# SIM_INTERFACE.net
KiCad netlist of a schematic drawn in Altium Designer
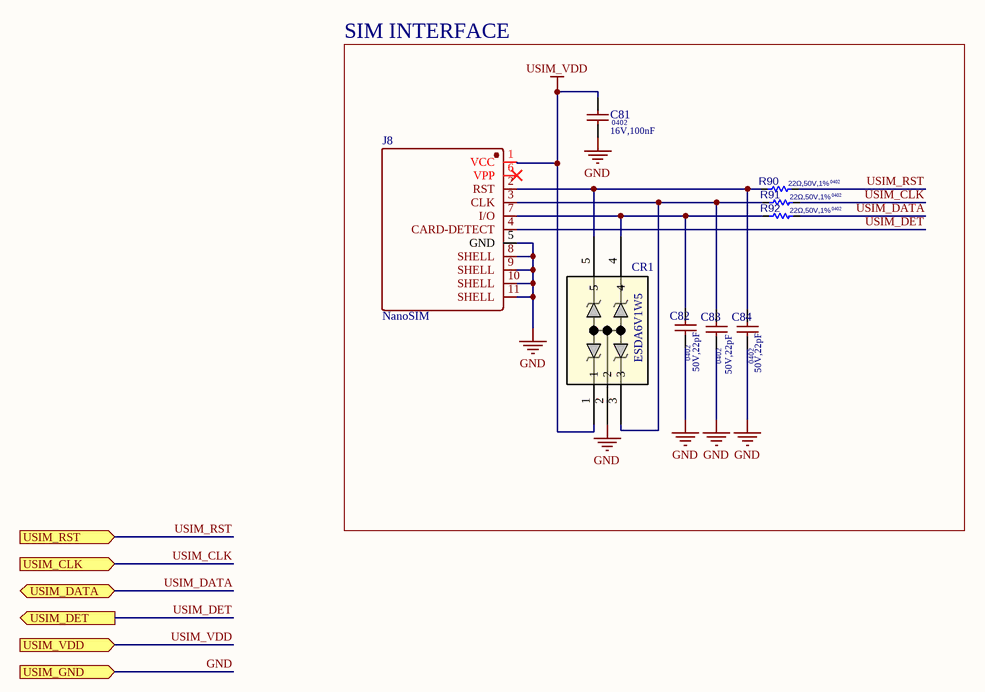
[diagram p0: SIM_INTERFACE.SchDoc]

(export (version "E")
  (design (tool "Eeschema 10.0.6"))
  (components
    (comp (ref "C81")
      (value "16V,100nF")
      (footprint "C0402")
      (description "16V 100nF X7R ±10% 0402 Multilayer Ceramic Capacitors MLCC - SMD/SMT ROHS")
      (fields
        (field (name "MANUFACTURER") "KEMET")
        (field (name "MPN") "CC0603KRX7R9BB104")
        (field (name "PACKAGE") "0402")
      )
      (libsource (lib "RCL") (part "CL05B104KO5NNNC"))
    )
    (comp (ref "C82")
      (value "50V,22pF")
      (footprint "C0402")
      (description "50V 22pF C0G ±5% 0402 Multilayer Ceramic Capacitors MLCC - SMD/SMT ROHS")
      (fields
        (field (name "MANUFACTURER") "KEMET")
        (field (name "MPN") "CC0603KRX7R9BB104")
        (field (name "PACKAGE") "0402")
      )
      (libsource (lib "RCL") (part "0402CG220J500NT"))
    )
    (comp (ref "C83")
      (value "50V,22pF")
      (footprint "C0402")
      (description "50V 22pF C0G ±5% 0402 Multilayer Ceramic Capacitors MLCC - SMD/SMT ROHS")
      (fields
        (field (name "MANUFACTURER") "KEMET")
        (field (name "MPN") "CC0603KRX7R9BB104")
        (field (name "PACKAGE") "0402")
      )
      (libsource (lib "RCL") (part "0402CG220J500NT"))
    )
    (comp (ref "C84")
      (value "50V,22pF")
      (footprint "C0402")
      (description "50V 22pF C0G ±5% 0402 Multilayer Ceramic Capacitors MLCC - SMD/SMT ROHS")
      (fields
        (field (name "MANUFACTURER") "KEMET")
        (field (name "MPN") "CC0603KRX7R9BB104")
        (field (name "PACKAGE") "0402")
      )
      (libsource (lib "RCL") (part "0402CG220J500NT"))
    )
    (comp (ref "CR1")
      (value "ESDA6V1W5")
      (footprint "SOT323-5L_STM")
      (description "Clamp Ipp Tvs Diode Surface Mount SOT-323-5")
      (fields (field (name "MANUFACTURER") "STMicroelectronics"))
      (libsource (lib "IC") (part "ESDA6V1W5"))
    )
    (comp (ref "J8")
      (value "NanoSIM")
      (footprint "XKNANO-113")
      (fields (field (name "MPN") "XKNANO-113"))
      (libsource (lib "connector_button") (part "XKNANO-113"))
    )
    (comp (ref "R90")
      (value "22Ω,50V,1%")
      (footprint "R0402")
      (description "62.5mW Thick Film Resistors 50V ±100ppm/℃ ±1% 22Ω 0402 Chip Resistor - Surface Mount ROHS")
      (fields
        (field (name "MANUFACTURER") "YAGEO")
        (field (name "MPN") "RC0402FR-0722RL")
        (field (name "PACKAGE") "0402")
      )
      (libsource (lib "RCL") (part "RC0402FR-0722RL"))
    )
    (comp (ref "R91")
      (value "22Ω,50V,1%")
      (footprint "R0402")
      (description "62.5mW Thick Film Resistors 50V ±100ppm/℃ ±1% 22Ω 0402 Chip Resistor - Surface Mount ROHS")
      (fields
        (field (name "MANUFACTURER") "YAGEO")
        (field (name "MPN") "RC0402FR-0722RL")
        (field (name "PACKAGE") "0402")
      )
      (libsource (lib "RCL") (part "RC0402FR-0722RL"))
    )
    (comp (ref "R92")
      (value "22Ω,50V,1%")
      (footprint "R0402")
      (description "62.5mW Thick Film Resistors 50V ±100ppm/℃ ±1% 22Ω 0402 Chip Resistor - Surface Mount ROHS")
      (fields
        (field (name "MANUFACTURER") "YAGEO")
        (field (name "MPN") "RC0402FR-0722RL")
        (field (name "PACKAGE") "0402")
      )
      (libsource (lib "RCL") (part "RC0402FR-0722RL"))
    )
  )
  (nets
    (net (code "1") (name "/USIM_CLK") (class "Default")
      (node (ref "R91") (pin "2") (pinfunction "2_2") (pintype "passive"))
    )
    (net (code "2") (name "/USIM_DATA") (class "Default")
      (node (ref "R92") (pin "2") (pinfunction "2_2") (pintype "passive"))
    )
    (net (code "3") (name "/USIM_DET") (class "Default")
      (node (ref "J8") (pin "4") (pinfunction "CARD-DETECT_4") (pintype "passive"))
    )
    (net (code "4") (name "/USIM_RST") (class "Default")
      (node (ref "R90") (pin "2") (pinfunction "2_2") (pintype "passive"))
    )
    (net (code "5") (name "GND") (class "Default")
      (node (ref "C81") (pin "1") (pinfunction "1_1") (pintype "passive"))
      (node (ref "C82") (pin "1") (pinfunction "1_1") (pintype "passive"))
      (node (ref "C83") (pin "1") (pinfunction "1_1") (pintype "passive"))
      (node (ref "C84") (pin "1") (pinfunction "1_1") (pintype "passive"))
      (node (ref "CR1") (pin "2") (pinfunction "2_2") (pintype "passive"))
      (node (ref "J8") (pin "10") (pinfunction "SHELL_10") (pintype "passive"))
      (node (ref "J8") (pin "11") (pinfunction "SHELL_11") (pintype "passive"))
      (node (ref "J8") (pin "5") (pinfunction "GND_5") (pintype "passive"))
      (node (ref "J8") (pin "8") (pinfunction "SHELL_8") (pintype "passive"))
      (node (ref "J8") (pin "9") (pinfunction "SHELL_9") (pintype "passive"))
    )
    (net (code "6") (name "Net-(J8-CLK)") (class "Default")
      (node (ref "C83") (pin "2") (pinfunction "2_2") (pintype "passive"))
      (node (ref "CR1") (pin "3") (pinfunction "3_3") (pintype "passive"))
      (node (ref "J8") (pin "3") (pinfunction "CLK_3") (pintype "passive"))
      (node (ref "R91") (pin "1") (pinfunction "1_1") (pintype "passive"))
    )
    (net (code "7") (name "Net-(J8-I{slash}O)") (class "Default")
      (node (ref "C82") (pin "2") (pinfunction "2_2") (pintype "passive"))
      (node (ref "CR1") (pin "4") (pinfunction "4_4") (pintype "passive"))
      (node (ref "J8") (pin "7") (pinfunction "I/O_7") (pintype "passive"))
      (node (ref "R92") (pin "1") (pinfunction "1_1") (pintype "passive"))
    )
    (net (code "8") (name "Net-(J8-RST)") (class "Default")
      (node (ref "C84") (pin "2") (pinfunction "2_2") (pintype "passive"))
      (node (ref "CR1") (pin "5") (pinfunction "5_5") (pintype "passive"))
      (node (ref "J8") (pin "2") (pinfunction "RST_2") (pintype "passive"))
      (node (ref "R90") (pin "1") (pinfunction "1_1") (pintype "passive"))
    )
    (net (code "9") (name "USIM_VDD") (class "Default")
      (node (ref "C81") (pin "2") (pinfunction "2_2") (pintype "passive"))
      (node (ref "CR1") (pin "1") (pinfunction "1_1") (pintype "passive"))
      (node (ref "J8") (pin "1") (pinfunction "VCC_1") (pintype "passive"))
    )
    (net (code "10") (name "unconnected-(J8-VPP-Pad6)") (class "Default")
      (node (ref "J8") (pin "6") (pinfunction "VPP_6") (pintype "passive+no_connect"))
    )
  )
)
